# GSM_INTERFACE.net
KiCad netlist of a schematic drawn in Altium Designer
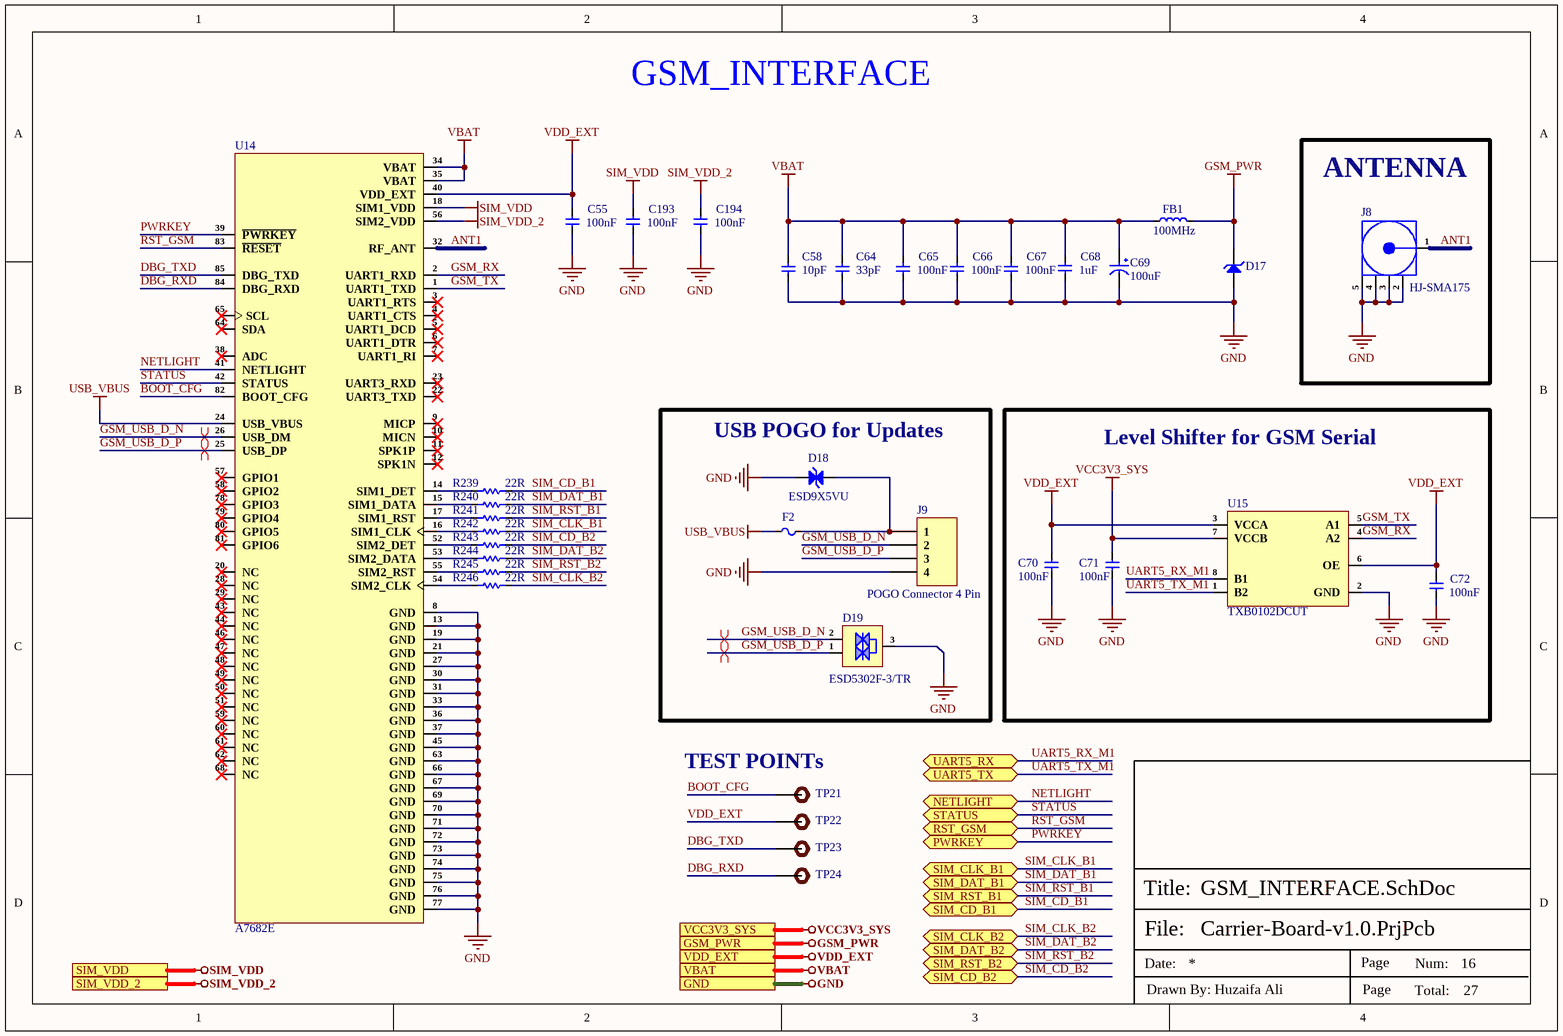
[diagram p0: GSM_INTERFACE.SchDoc]

(export (version "E")
  (design (tool "Eeschema 10.0.6"))
  (components
    (comp (ref "C55")
      (value "100nF")
      (footprint "Cap-0402")
      (description "CAP CER 0.1UF 16V X5R 0402")
      (fields
        (field (name "MANUFACTURER") "Yageo")
        (field (name "MANUFACTURER PART NUMBER") "CC0402KRX5R7BB104")
      )
      (libsource (lib "eSpark Libraries") (part "CC0402KRX5R7BB104"))
    )
    (comp (ref "C58")
      (value "10pF")
      (footprint "Cap-0402")
      (description "CAP CER 10PF 50V C0G/NP0 0402")
      (fields
        (field (name "MANUFACTURER") "Murata")
        (field (name "MANUFACTURER PART NUMBER") "GRM1555C1H100JA01D")
      )
      (libsource (lib "eSpark Libraries") (part "GRM1555C1H100JA01D"))
    )
    (comp (ref "C64")
      (value "33pF")
      (footprint "Cap-0402")
      (description "CAP CER 33PF 25V C0G/NP0 0402")
      (fields
        (field (name "MANUFACTURER") "Murata")
        (field (name "MANUFACTURER PART NUMBER") "GRM1555C1E330JA01D")
      )
      (libsource (lib "eSpark Libraries") (part "GRM1555C1E330JA01D"))
    )
    (comp (ref "C65")
      (value "100nF")
      (footprint "Cap-0402")
      (description "CAP CER 0.1UF 16V X5R 0402")
      (fields
        (field (name "MANUFACTURER") "Yageo")
        (field (name "MANUFACTURER PART NUMBER") "CC0402KRX5R7BB104")
      )
      (libsource (lib "eSpark Libraries") (part "CC0402KRX5R7BB104"))
    )
    (comp (ref "C66")
      (value "100nF")
      (footprint "Cap-0402")
      (description "CAP CER 0.1UF 16V X5R 0402")
      (fields
        (field (name "MANUFACTURER") "Yageo")
        (field (name "MANUFACTURER PART NUMBER") "CC0402KRX5R7BB104")
      )
      (libsource (lib "eSpark Libraries") (part "CC0402KRX5R7BB104"))
    )
    (comp (ref "C67")
      (value "100nF")
      (footprint "Cap-0402")
      (description "CAP CER 0.1UF 16V X5R 0402")
      (fields
        (field (name "MANUFACTURER") "Yageo")
        (field (name "MANUFACTURER PART NUMBER") "CC0402KRX5R7BB104")
      )
      (libsource (lib "eSpark Libraries") (part "CC0402KRX5R7BB104"))
    )
    (comp (ref "C68")
      (value "1uF")
      (footprint "Cap-0402")
      (description "CAP CER 1UF 25V X5R 0402")
      (fields
        (field (name "MANUFACTURER") "Yageo")
        (field (name "MANUFACTURER PART NUMBER") "CC0402KRX5R8BB105")
      )
      (libsource (lib "eSpark Libraries") (part "CC0402KRX5R8BB105"))
    )
    (comp (ref "C69")
      (value "100uF")
      (footprint "Case-B")
      (description "CAP TANT 100UF 20% 10V 1411")
      (fields
        (field (name "MANUFACTURER") "Kyocera AVX")
        (field (name "MANUFACTURER PART NUMBER") "TAJB107M010RNJ")
      )
      (libsource (lib "eSpark Libraries") (part "TAJB107M010RNJ"))
    )
    (comp (ref "C70")
      (value "100nF")
      (footprint "Cap-0402")
      (description "CAP CER 0.1UF 16V X5R 0402")
      (fields
        (field (name "MANUFACTURER") "Yageo")
        (field (name "MANUFACTURER PART NUMBER") "CC0402KRX5R7BB104")
      )
      (libsource (lib "eSpark Libraries") (part "CC0402KRX5R7BB104"))
    )
    (comp (ref "C71")
      (value "100nF")
      (footprint "Cap-0402")
      (description "CAP CER 0.1UF 16V X5R 0402")
      (fields
        (field (name "MANUFACTURER") "Yageo")
        (field (name "MANUFACTURER PART NUMBER") "CC0402KRX5R7BB104")
      )
      (libsource (lib "eSpark Libraries") (part "CC0402KRX5R7BB104"))
    )
    (comp (ref "C72")
      (value "100nF")
      (footprint "Cap-0402")
      (description "CAP CER 0.1UF 16V X5R 0402")
      (fields
        (field (name "MANUFACTURER") "Yageo")
        (field (name "MANUFACTURER PART NUMBER") "CC0402KRX5R7BB104")
      )
      (libsource (lib "eSpark Libraries") (part "CC0402KRX5R7BB104"))
    )
    (comp (ref "C193")
      (value "100nF")
      (footprint "Cap-0402")
      (description "CAP CER 0.1UF 16V X5R 0402")
      (fields
        (field (name "MANUFACTURER") "Yageo")
        (field (name "MANUFACTURER PART NUMBER") "CC0402KRX5R7BB104")
      )
      (libsource (lib "eSpark Libraries") (part "CC0402KRX5R7BB104"))
    )
    (comp (ref "C194")
      (value "100nF")
      (footprint "Cap-0402")
      (description "CAP CER 0.1UF 16V X5R 0402")
      (fields
        (field (name "MANUFACTURER") "Yageo")
        (field (name "MANUFACTURER PART NUMBER") "CC0402KRX5R7BB104")
      )
      (libsource (lib "eSpark Libraries") (part "CC0402KRX5R7BB104"))
    )
    (comp (ref "D17")
      (value "MMSZ5231BT1G")
      (footprint "SOD-123")
      (description "DIODE ZENER 5.1V 500MW SOD123")
      (fields (field (name "MANUFACTURER") "ON Semiconductor") (field (name "TOLERANCE") "5%"))
      (libsource (lib "eSpark Libraries") (part "MMSZ5231BT1G"))
    )
    (comp (ref "D18")
      (value "ESD9X5VU")
      (footprint "DFN1006-2L_")
      (description "DFN1006-2 ESD Protection Devices ROHS")
      (fields (field (name "MANUFACTURER") "TECH PUBLIC") (field (name "LCSC PART NUMBER") "C2875160"))
      (libsource (lib "eSpark Libraries") (part "ESD9X5VU"))
    )
    (comp (ref "D19")
      (value "ESD5302F-3/TR")
      (footprint "Sot-23")
      (description "16A 20V 7V 5V@Max Unidirectional SOT-23 TVS ROHS")
      (fields (field (name "MANUFACTURER") "WILLSEMI") (field (name "LCSC PART NUMBER") "C239643"))
      (libsource (lib "eSpark Libraries") (part "ESD5302F-3/TR"))
    )
    (comp (ref "F2")
      (value "SMD0603-050")
      (footprint "Fuse-0603")
      (description "6V 500mA 40A 1A 0603 Resettable Fuses ROHS")
      (fields (field (name "MANUFACTURER") "TECHFUSE") (field (name "LCSC PART NUMBER") "C69679"))
      (libsource (lib "eSpark Libraries") (part "SMD0603-050"))
    )
    (comp (ref "FB1")
      (value "100MHz")
      (footprint "Ind-0805")
      (description "FERRITE BEAD 30 OHM 0805 1LN")
      (fields (field (name "LCSC PART NUMBER") "C16903") (field (name "TOLERANCE") "25%"))
      (libsource (lib "eSpark Libraries") (part "BLM21PG300SN1D"))
    )
    (comp (ref "J8")
      (value "HJ-SMA175")
      (footprint "HJ-SMA175")
      (description "1 Inner bore SMA Board Edge Bend 11mm 5.35mm Plugin RF Connectors / Coaxial Connectors ROHS")
      (fields (field (name "MANUFACTURER") "HJ Tech") (field (name "LCSC PART NUMBER") "C1509213"))
      (libsource (lib "eSpark Libraries") (part "HJ-SMA175"))
    )
    (comp (ref "J9")
      (value "POGO Connector 4 Pin")
      (footprint "Pogo 4 Pin")
      (description "Pogo Pad 2.5mm 4 Pin")
      (libsource (lib "eSpark_centralized_Library(2022)") (part "POGO Connector 4 Pin"))
    )
    (comp (ref "R239")
      (value "22R")
      (footprint "Res-0402")
      (description "RES 22 OHM 1% 1/16W 0402")
      (fields
        (field (name "MANUFACTURER") "Yageo")
        (field (name "MANUFACTURER PART NUMBER") "RC0402FR-0722RL")
      )
      (libsource (lib "eSpark Libraries") (part "RC0402FR-0722RL"))
    )
    (comp (ref "R240")
      (value "22R")
      (footprint "Res-0402")
      (description "RES 22 OHM 1% 1/16W 0402")
      (fields
        (field (name "MANUFACTURER") "Yageo")
        (field (name "MANUFACTURER PART NUMBER") "RC0402FR-0722RL")
      )
      (libsource (lib "eSpark Libraries") (part "RC0402FR-0722RL"))
    )
    (comp (ref "R241")
      (value "22R")
      (footprint "Res-0402")
      (description "RES 22 OHM 1% 1/16W 0402")
      (fields
        (field (name "MANUFACTURER") "Yageo")
        (field (name "MANUFACTURER PART NUMBER") "RC0402FR-0722RL")
      )
      (libsource (lib "eSpark Libraries") (part "RC0402FR-0722RL"))
    )
    (comp (ref "R242")
      (value "22R")
      (footprint "Res-0402")
      (description "RES 22 OHM 1% 1/16W 0402")
      (fields
        (field (name "MANUFACTURER") "Yageo")
        (field (name "MANUFACTURER PART NUMBER") "RC0402FR-0722RL")
      )
      (libsource (lib "eSpark Libraries") (part "RC0402FR-0722RL"))
    )
    (comp (ref "R243")
      (value "22R")
      (footprint "Res-0402")
      (description "RES 22 OHM 1% 1/16W 0402")
      (fields
        (field (name "MANUFACTURER") "Yageo")
        (field (name "MANUFACTURER PART NUMBER") "RC0402FR-0722RL")
      )
      (libsource (lib "eSpark Libraries") (part "RC0402FR-0722RL"))
    )
    (comp (ref "R244")
      (value "22R")
      (footprint "Res-0402")
      (description "RES 22 OHM 1% 1/16W 0402")
      (fields
        (field (name "MANUFACTURER") "Yageo")
        (field (name "MANUFACTURER PART NUMBER") "RC0402FR-0722RL")
      )
      (libsource (lib "eSpark Libraries") (part "RC0402FR-0722RL"))
    )
    (comp (ref "R245")
      (value "22R")
      (footprint "Res-0402")
      (description "RES 22 OHM 1% 1/16W 0402")
      (fields
        (field (name "MANUFACTURER") "Yageo")
        (field (name "MANUFACTURER PART NUMBER") "RC0402FR-0722RL")
      )
      (libsource (lib "eSpark Libraries") (part "RC0402FR-0722RL"))
    )
    (comp (ref "R246")
      (value "22R")
      (footprint "Res-0402")
      (description "RES 22 OHM 1% 1/16W 0402")
      (fields
        (field (name "MANUFACTURER") "Yageo")
        (field (name "MANUFACTURER PART NUMBER") "RC0402FR-0722RL")
      )
      (libsource (lib "eSpark Libraries") (part "RC0402FR-0722RL"))
    )
    (comp (ref "TP21")
      (value "TEST POINT 0.5mm Dia")
      (footprint "Test-point - 0.5mm")
      (description "Test Point ON")
      (libsource (lib "eSpark Libraries") (part "TEST POINT 0.5mm Dia"))
    )
    (comp (ref "TP22")
      (value "TEST POINT 0.5mm Dia")
      (footprint "Test-point - 0.5mm")
      (description "Test Point ON")
      (libsource (lib "eSpark Libraries") (part "TEST POINT 0.5mm Dia"))
    )
    (comp (ref "TP23")
      (value "TEST POINT 0.5mm Dia")
      (footprint "Test-point - 0.5mm")
      (description "Test Point ON")
      (libsource (lib "eSpark Libraries") (part "TEST POINT 0.5mm Dia"))
    )
    (comp (ref "TP24")
      (value "TEST POINT 0.5mm Dia")
      (footprint "Test-point - 0.5mm")
      (description "Test Point ON")
      (libsource (lib "eSpark Libraries") (part "TEST POINT 0.5mm Dia"))
    )
    (comp (ref "U14")
      (value "A7682E")
      (footprint "A7682E")
      (description "LGA-85_19.6x19.6x1.10P RF Modules ROHS")
      (fields
        (field (name "MANUFACTURER") "SIMCom Wireless Solutions")
        (field (name "LCSC PART NUMBER") "C5362858")
      )
      (libsource (lib "eSpark Libraries") (part "A7682E"))
    )
    (comp (ref "U15")
      (value "TXB0102DCUT")
      (footprint "TXB0102DCUT")
      (description "IC TRNSLTR BIDIRECTIONAL US8")
      (fields (field (name "MANUFACTURER") "Texas Instruments"))
      (libsource (lib "eSpark Libraries") (part "TXB0102DCUT"))
    )
  )
  (nets
    (net (code "1") (name "/ANT1") (class "Default")
      (node (ref "J8") (pin "1") (pinfunction "Signal_1") (pintype "passive"))
      (node (ref "U14") (pin "32") (pinfunction "RF_ANT_32") (pintype "passive"))
    )
    (net (code "2") (name "/BOOT_CFG") (class "Default")
      (node (ref "TP21") (pin "1") (pinfunction "1_1") (pintype "passive"))
      (node (ref "U14") (pin "82") (pinfunction "BOOT_CFG_82") (pintype "passive"))
    )
    (net (code "3") (name "/DBG_RXD") (class "Default")
      (node (ref "TP24") (pin "1") (pinfunction "1_1") (pintype "passive"))
      (node (ref "U14") (pin "84") (pinfunction "DBG_RXD_84") (pintype "passive"))
    )
    (net (code "4") (name "/DBG_TXD") (class "Default")
      (node (ref "TP23") (pin "1") (pinfunction "1_1") (pintype "passive"))
      (node (ref "U14") (pin "85") (pinfunction "DBG_TXD_85") (pintype "passive"))
    )
    (net (code "5") (name "/GSM_RX") (class "Default")
      (node (ref "U14") (pin "2") (pinfunction "UART1_RXD_2") (pintype "passive"))
      (node (ref "U15") (pin "4") (pinfunction "A2_4") (pintype "passive"))
    )
    (net (code "6") (name "/GSM_TX") (class "Default")
      (node (ref "U14") (pin "1") (pinfunction "UART1_TXD_1") (pintype "passive"))
      (node (ref "U15") (pin "5") (pinfunction "A1_5") (pintype "passive"))
    )
    (net (code "7") (name "/GSM_USB_D_N") (class "Default")
      (node (ref "D19") (pin "2") (pinfunction "I/O2_2") (pintype "passive"))
      (node (ref "J9") (pin "2") (pinfunction "2_2") (pintype "passive"))
      (node (ref "U14") (pin "26") (pinfunction "USB_DM_26") (pintype "passive"))
    )
    (net (code "8") (name "/GSM_USB_D_P") (class "Default")
      (node (ref "D19") (pin "1") (pinfunction "I/O1_1") (pintype "passive"))
      (node (ref "J9") (pin "3") (pinfunction "3_3") (pintype "passive"))
      (node (ref "U14") (pin "25") (pinfunction "USB_DP_25") (pintype "passive"))
    )
    (net (code "9") (name "/NETLIGHT") (class "Default")
      (node (ref "U14") (pin "41") (pinfunction "NETLIGHT_41") (pintype "passive"))
    )
    (net (code "10") (name "/PWRKEY") (class "Default")
      (node (ref "U14") (pin "39") (pinfunction "~{PWRKEY}_39") (pintype "passive"))
    )
    (net (code "11") (name "/RST_GSM") (class "Default")
      (node (ref "U14") (pin "83") (pinfunction "~{RESET}_83") (pintype "passive"))
    )
    (net (code "12") (name "/SIM_CD_B1") (class "Default")
      (node (ref "R239") (pin "2") (pinfunction "2_2") (pintype "passive"))
    )
    (net (code "13") (name "/SIM_CD_B2") (class "Default")
      (node (ref "R243") (pin "2") (pinfunction "2_2") (pintype "passive"))
    )
    (net (code "14") (name "/SIM_CLK_B1") (class "Default")
      (node (ref "R242") (pin "2") (pinfunction "2_2") (pintype "passive"))
    )
    (net (code "15") (name "/SIM_CLK_B2") (class "Default")
      (node (ref "R246") (pin "2") (pinfunction "2_2") (pintype "passive"))
    )
    (net (code "16") (name "/SIM_DAT_B1") (class "Default")
      (node (ref "R240") (pin "2") (pinfunction "2_2") (pintype "passive"))
    )
    (net (code "17") (name "/SIM_DAT_B2") (class "Default")
      (node (ref "R244") (pin "2") (pinfunction "2_2") (pintype "passive"))
    )
    (net (code "18") (name "/SIM_RST_B1") (class "Default")
      (node (ref "R241") (pin "2") (pinfunction "2_2") (pintype "passive"))
    )
    (net (code "19") (name "/SIM_RST_B2") (class "Default")
      (node (ref "R245") (pin "2") (pinfunction "2_2") (pintype "passive"))
    )
    (net (code "20") (name "/STATUS") (class "Default")
      (node (ref "U14") (pin "42") (pinfunction "STATUS_42") (pintype "passive"))
    )
    (net (code "21") (name "/UART5_RX_M1") (class "Default")
      (node (ref "U15") (pin "8") (pinfunction "B1_8") (pintype "passive"))
    )
    (net (code "22") (name "/UART5_TX_M1") (class "Default")
      (node (ref "U15") (pin "1") (pinfunction "B2_1") (pintype "passive"))
    )
    (net (code "23") (name "GND") (class "Default")
      (node (ref "C193") (pin "1") (pinfunction "1_1") (pintype "passive"))
      (node (ref "C194") (pin "1") (pinfunction "1_1") (pintype "passive"))
      (node (ref "C55") (pin "1") (pinfunction "1_1") (pintype "passive"))
      (node (ref "C58") (pin "1") (pinfunction "1_1") (pintype "passive"))
      (node (ref "C64") (pin "1") (pinfunction "1_1") (pintype "passive"))
      (node (ref "C65") (pin "1") (pinfunction "1_1") (pintype "passive"))
      (node (ref "C66") (pin "1") (pinfunction "1_1") (pintype "passive"))
      (node (ref "C67") (pin "1") (pinfunction "1_1") (pintype "passive"))
      (node (ref "C68") (pin "2") (pinfunction "2_2") (pintype "passive"))
      (node (ref "C69") (pin "2") (pinfunction "2_2") (pintype "passive"))
      (node (ref "C70") (pin "2") (pinfunction "2_2") (pintype "passive"))
      (node (ref "C71") (pin "2") (pinfunction "2_2") (pintype "passive"))
      (node (ref "C72") (pin "1") (pinfunction "1_1") (pintype "passive"))
      (node (ref "D17") (pin "1") (pinfunction "A_1") (pintype "passive"))
      (node (ref "D18") (pin "1") (pinfunction "A_1") (pintype "passive"))
      (node (ref "D19") (pin "3") (pinfunction "GND_3") (pintype "passive"))
      (node (ref "J8") (pin "2") (pinfunction "GND_2") (pintype "passive"))
      (node (ref "J8") (pin "3") (pinfunction "GND_3") (pintype "passive"))
      (node (ref "J8") (pin "4") (pinfunction "GND_4") (pintype "passive"))
      (node (ref "J8") (pin "5") (pinfunction "GND_5") (pintype "passive"))
      (node (ref "J9") (pin "4") (pinfunction "4_4") (pintype "passive"))
      (node (ref "U14") (pin "13") (pinfunction "GND_13") (pintype "passive"))
      (node (ref "U14") (pin "19") (pinfunction "GND_19") (pintype "passive"))
      (node (ref "U14") (pin "21") (pinfunction "GND_21") (pintype "passive"))
      (node (ref "U14") (pin "27") (pinfunction "GND_27") (pintype "passive"))
      (node (ref "U14") (pin "30") (pinfunction "GND_30") (pintype "passive"))
      (node (ref "U14") (pin "31") (pinfunction "GND_31") (pintype "passive"))
      (node (ref "U14") (pin "33") (pinfunction "GND_33") (pintype "passive"))
      (node (ref "U14") (pin "36") (pinfunction "GND_36") (pintype "passive"))
      (node (ref "U14") (pin "37") (pinfunction "GND_37") (pintype "passive"))
      (node (ref "U14") (pin "45") (pinfunction "GND_45") (pintype "passive"))
      (node (ref "U14") (pin "63") (pinfunction "GND_63") (pintype "passive"))
      (node (ref "U14") (pin "66") (pinfunction "GND_66") (pintype "passive"))
      (node (ref "U14") (pin "67") (pinfunction "GND_67") (pintype "passive"))
      (node (ref "U14") (pin "69") (pinfunction "GND_69") (pintype "passive"))
      (node (ref "U14") (pin "70") (pinfunction "GND_70") (pintype "passive"))
      (node (ref "U14") (pin "71") (pinfunction "GND_71") (pintype "passive"))
      (node (ref "U14") (pin "72") (pinfunction "GND_72") (pintype "passive"))
      (node (ref "U14") (pin "73") (pinfunction "GND_73") (pintype "passive"))
      (node (ref "U14") (pin "74") (pinfunction "GND_74") (pintype "passive"))
      (node (ref "U14") (pin "75") (pinfunction "GND_75") (pintype "passive"))
      (node (ref "U14") (pin "76") (pinfunction "GND_76") (pintype "passive"))
      (node (ref "U14") (pin "77") (pinfunction "GND_77") (pintype "passive"))
      (node (ref "U14") (pin "8") (pinfunction "GND_8") (pintype "passive"))
      (node (ref "U15") (pin "2") (pinfunction "GND_2") (pintype "passive"))
    )
    (net (code "24") (name "GSM_PWR") (class "Default")
      (node (ref "D17") (pin "2") (pinfunction "K_2") (pintype "passive"))
      (node (ref "FB1") (pin "2") (pinfunction "2_2") (pintype "passive"))
    )
    (net (code "25") (name "Net-(D18-A-Pad2)") (class "Default")
      (node (ref "D18") (pin "2") (pinfunction "A_2") (pintype "passive"))
      (node (ref "F2") (pin "2") (pinfunction "2_2") (pintype "passive"))
      (node (ref "J9") (pin "1") (pinfunction "1_1") (pintype "passive"))
    )
    (net (code "26") (name "Net-(U14-SIM1_CLK)") (class "Default")
      (node (ref "R242") (pin "1") (pinfunction "1_1") (pintype "passive"))
      (node (ref "U14") (pin "16") (pinfunction "SIM1_CLK_16") (pintype "passive"))
    )
    (net (code "27") (name "Net-(U14-SIM1_DATA)") (class "Default")
      (node (ref "R240") (pin "1") (pinfunction "1_1") (pintype "passive"))
      (node (ref "U14") (pin "15") (pinfunction "SIM1_DATA_15") (pintype "passive"))
    )
    (net (code "28") (name "Net-(U14-SIM1_DET)") (class "Default")
      (node (ref "R239") (pin "1") (pinfunction "1_1") (pintype "passive"))
      (node (ref "U14") (pin "14") (pinfunction "SIM1_DET_14") (pintype "passive"))
    )
    (net (code "29") (name "Net-(U14-SIM1_RST)") (class "Default")
      (node (ref "R241") (pin "1") (pinfunction "1_1") (pintype "passive"))
      (node (ref "U14") (pin "17") (pinfunction "SIM1_RST_17") (pintype "passive"))
    )
    (net (code "30") (name "Net-(U14-SIM2_CLK)") (class "Default")
      (node (ref "R246") (pin "1") (pinfunction "1_1") (pintype "passive"))
      (node (ref "U14") (pin "54") (pinfunction "SIM2_CLK_54") (pintype "passive"))
    )
    (net (code "31") (name "Net-(U14-SIM2_DATA)") (class "Default")
      (node (ref "R244") (pin "1") (pinfunction "1_1") (pintype "passive"))
      (node (ref "U14") (pin "53") (pinfunction "SIM2_DATA_53") (pintype "passive"))
    )
    (net (code "32") (name "Net-(U14-SIM2_DET)") (class "Default")
      (node (ref "R243") (pin "1") (pinfunction "1_1") (pintype "passive"))
      (node (ref "U14") (pin "52") (pinfunction "SIM2_DET_52") (pintype "passive"))
    )
    (net (code "33") (name "Net-(U14-SIM2_RST)") (class "Default")
      (node (ref "R245") (pin "1") (pinfunction "1_1") (pintype "passive"))
      (node (ref "U14") (pin "55") (pinfunction "SIM2_RST_55") (pintype "passive"))
    )
    (net (code "34") (name "SIM_VDD") (class "Default")
      (node (ref "C193") (pin "2") (pinfunction "2_2") (pintype "passive"))
      (node (ref "U14") (pin "18") (pinfunction "SIM1_VDD_18") (pintype "passive"))
    )
    (net (code "35") (name "SIM_VDD_2") (class "Default")
      (node (ref "C194") (pin "2") (pinfunction "2_2") (pintype "passive"))
      (node (ref "U14") (pin "56") (pinfunction "SIM2_VDD_56") (pintype "passive"))
    )
    (net (code "36") (name "USB_VBUS") (class "Default")
      (node (ref "F2") (pin "1") (pinfunction "1_1") (pintype "passive"))
      (node (ref "U14") (pin "24") (pinfunction "USB_VBUS_24") (pintype "passive"))
    )
    (net (code "37") (name "VBAT") (class "Default")
      (node (ref "C58") (pin "2") (pinfunction "2_2") (pintype "passive"))
      (node (ref "C64") (pin "2") (pinfunction "2_2") (pintype "passive"))
      (node (ref "C65") (pin "2") (pinfunction "2_2") (pintype "passive"))
      (node (ref "C66") (pin "2") (pinfunction "2_2") (pintype "passive"))
      (node (ref "C67") (pin "2") (pinfunction "2_2") (pintype "passive"))
      (node (ref "C68") (pin "1") (pinfunction "1_1") (pintype "passive"))
      (node (ref "C69") (pin "1") (pinfunction "1_1") (pintype "passive"))
      (node (ref "FB1") (pin "1") (pinfunction "1_1") (pintype "passive"))
      (node (ref "U14") (pin "34") (pinfunction "VBAT_34") (pintype "passive"))
      (node (ref "U14") (pin "35") (pinfunction "VBAT_35") (pintype "passive"))
    )
    (net (code "38") (name "VCC3V3_SYS") (class "Default")
      (node (ref "C71") (pin "1") (pinfunction "1_1") (pintype "passive"))
      (node (ref "U15") (pin "7") (pinfunction "VCCB_7") (pintype "passive"))
    )
    (net (code "39") (name "VDD_EXT") (class "Default")
      (node (ref "C55") (pin "2") (pinfunction "2_2") (pintype "passive"))
      (node (ref "C70") (pin "1") (pinfunction "1_1") (pintype "passive"))
      (node (ref "C72") (pin "2") (pinfunction "2_2") (pintype "passive"))
      (node (ref "TP22") (pin "1") (pinfunction "1_1") (pintype "passive"))
      (node (ref "U14") (pin "40") (pinfunction "VDD_EXT_40") (pintype "passive"))
      (node (ref "U15") (pin "3") (pinfunction "VCCA_3") (pintype "passive"))
      (node (ref "U15") (pin "6") (pinfunction "OE_6") (pintype "passive"))
    )
    (net (code "40") (name "unconnected-(U14-ADC-Pad38)") (class "Default")
      (node (ref "U14") (pin "38") (pinfunction "ADC_38") (pintype "passive+no_connect"))
    )
    (net (code "41") (name "unconnected-(U14-GPIO1-Pad57)") (class "Default")
      (node (ref "U14") (pin "57") (pinfunction "GPIO1_57") (pintype "passive+no_connect"))
    )
    (net (code "42") (name "unconnected-(U14-GPIO2-Pad58)") (class "Default")
      (node (ref "U14") (pin "58") (pinfunction "GPIO2_58") (pintype "passive+no_connect"))
    )
    (net (code "43") (name "unconnected-(U14-GPIO3-Pad78)") (class "Default")
      (node (ref "U14") (pin "78") (pinfunction "GPIO3_78") (pintype "passive+no_connect"))
    )
    (net (code "44") (name "unconnected-(U14-GPIO4-Pad79)") (class "Default")
      (node (ref "U14") (pin "79") (pinfunction "GPIO4_79") (pintype "passive+no_connect"))
    )
    (net (code "45") (name "unconnected-(U14-GPIO5-Pad80)") (class "Default")
      (node (ref "U14") (pin "80") (pinfunction "GPIO5_80") (pintype "passive+no_connect"))
    )
    (net (code "46") (name "unconnected-(U14-GPIO6-Pad81)") (class "Default")
      (node (ref "U14") (pin "81") (pinfunction "GPIO6_81") (pintype "passive+no_connect"))
    )
    (net (code "47") (name "unconnected-(U14-MICN-Pad10)") (class "Default")
      (node (ref "U14") (pin "10") (pinfunction "MICN_10") (pintype "passive+no_connect"))
    )
    (net (code "48") (name "unconnected-(U14-MICP-Pad9)") (class "Default")
      (node (ref "U14") (pin "9") (pinfunction "MICP_9") (pintype "passive+no_connect"))
    )
    (net (code "49") (name "unconnected-(U14-NC-Pad20)") (class "Default")
      (node (ref "U14") (pin "20") (pinfunction "NC_20") (pintype "passive+no_connect"))
    )
    (net (code "50") (name "unconnected-(U14-NC-Pad28)") (class "Default")
      (node (ref "U14") (pin "28") (pinfunction "NC_28") (pintype "passive+no_connect"))
    )
    (net (code "51") (name "unconnected-(U14-NC-Pad29)") (class "Default")
      (node (ref "U14") (pin "29") (pinfunction "NC_29") (pintype "passive+no_connect"))
    )
    (net (code "52") (name "unconnected-(U14-NC-Pad43)") (class "Default")
      (node (ref "U14") (pin "43") (pinfunction "NC_43") (pintype "passive+no_connect"))
    )
    (net (code "53") (name "unconnected-(U14-NC-Pad44)") (class "Default")
      (node (ref "U14") (pin "44") (pinfunction "NC_44") (pintype "passive+no_connect"))
    )
    (net (code "54") (name "unconnected-(U14-NC-Pad46)") (class "Default")
      (node (ref "U14") (pin "46") (pinfunction "NC_46") (pintype "passive+no_connect"))
    )
    (net (code "55") (name "unconnected-(U14-NC-Pad47)") (class "Default")
      (node (ref "U14") (pin "47") (pinfunction "NC_47") (pintype "passive+no_connect"))
    )
    (net (code "56") (name "unconnected-(U14-NC-Pad48)") (class "Default")
      (node (ref "U14") (pin "48") (pinfunction "NC_48") (pintype "passive+no_connect"))
    )
    (net (code "57") (name "unconnected-(U14-NC-Pad49)") (class "Default")
      (node (ref "U14") (pin "49") (pinfunction "NC_49") (pintype "passive+no_connect"))
    )
    (net (code "58") (name "unconnected-(U14-NC-Pad50)") (class "Default")
      (node (ref "U14") (pin "50") (pinfunction "NC_50") (pintype "passive+no_connect"))
    )
    (net (code "59") (name "unconnected-(U14-NC-Pad51)") (class "Default")
      (node (ref "U14") (pin "51") (pinfunction "NC_51") (pintype "passive+no_connect"))
    )
    (net (code "60") (name "unconnected-(U14-NC-Pad59)") (class "Default")
      (node (ref "U14") (pin "59") (pinfunction "NC_59") (pintype "passive+no_connect"))
    )
    (net (code "61") (name "unconnected-(U14-NC-Pad60)") (class "Default")
      (node (ref "U14") (pin "60") (pinfunction "NC_60") (pintype "passive+no_connect"))
    )
    (net (code "62") (name "unconnected-(U14-NC-Pad61)") (class "Default")
      (node (ref "U14") (pin "61") (pinfunction "NC_61") (pintype "passive+no_connect"))
    )
    (net (code "63") (name "unconnected-(U14-NC-Pad62)") (class "Default")
      (node (ref "U14") (pin "62") (pinfunction "NC_62") (pintype "passive+no_connect"))
    )
    (net (code "64") (name "unconnected-(U14-NC-Pad68)") (class "Default")
      (node (ref "U14") (pin "68") (pinfunction "NC_68") (pintype "passive+no_connect"))
    )
    (net (code "65") (name "unconnected-(U14-SCL-Pad65)") (class "Default")
      (node (ref "U14") (pin "65") (pinfunction "SCL_65") (pintype "passive+no_connect"))
    )
    (net (code "66") (name "unconnected-(U14-SDA-Pad64)") (class "Default")
      (node (ref "U14") (pin "64") (pinfunction "SDA_64") (pintype "passive+no_connect"))
    )
    (net (code "67") (name "unconnected-(U14-SPK1N-Pad12)") (class "Default")
      (node (ref "U14") (pin "12") (pinfunction "SPK1N_12") (pintype "passive+no_connect"))
    )
    (net (code "68") (name "unconnected-(U14-SPK1P-Pad11)") (class "Default")
      (node (ref "U14") (pin "11") (pinfunction "SPK1P_11") (pintype "passive+no_connect"))
    )
    (net (code "69") (name "unconnected-(U14-UART1_CTS-Pad4)") (class "Default")
      (node (ref "U14") (pin "4") (pinfunction "UART1_CTS_4") (pintype "passive+no_connect"))
    )
    (net (code "70") (name "unconnected-(U14-UART1_DCD-Pad5)") (class "Default")
      (node (ref "U14") (pin "5") (pinfunction "UART1_DCD_5") (pintype "passive+no_connect"))
    )
    (net (code "71") (name "unconnected-(U14-UART1_DTR-Pad6)") (class "Default")
      (node (ref "U14") (pin "6") (pinfunction "UART1_DTR_6") (pintype "passive+no_connect"))
    )
    (net (code "72") (name "unconnected-(U14-UART1_RI-Pad7)") (class "Default")
      (node (ref "U14") (pin "7") (pinfunction "UART1_RI_7") (pintype "passive+no_connect"))
    )
    (net (code "73") (name "unconnected-(U14-UART1_RTS-Pad3)") (class "Default")
      (node (ref "U14") (pin "3") (pinfunction "UART1_RTS_3") (pintype "passive+no_connect"))
    )
    (net (code "74") (name "unconnected-(U14-UART3_RXD-Pad23)") (class "Default")
      (node (ref "U14") (pin "23") (pinfunction "UART3_RXD_23") (pintype "passive+no_connect"))
    )
    (net (code "75") (name "unconnected-(U14-UART3_TXD-Pad22)") (class "Default")
      (node (ref "U14") (pin "22") (pinfunction "UART3_TXD_22") (pintype "passive+no_connect"))
    )
  )
)
